# planeReceiverSchem_v2.net
KiCad netlist of a schematic drawn in Altium Designer
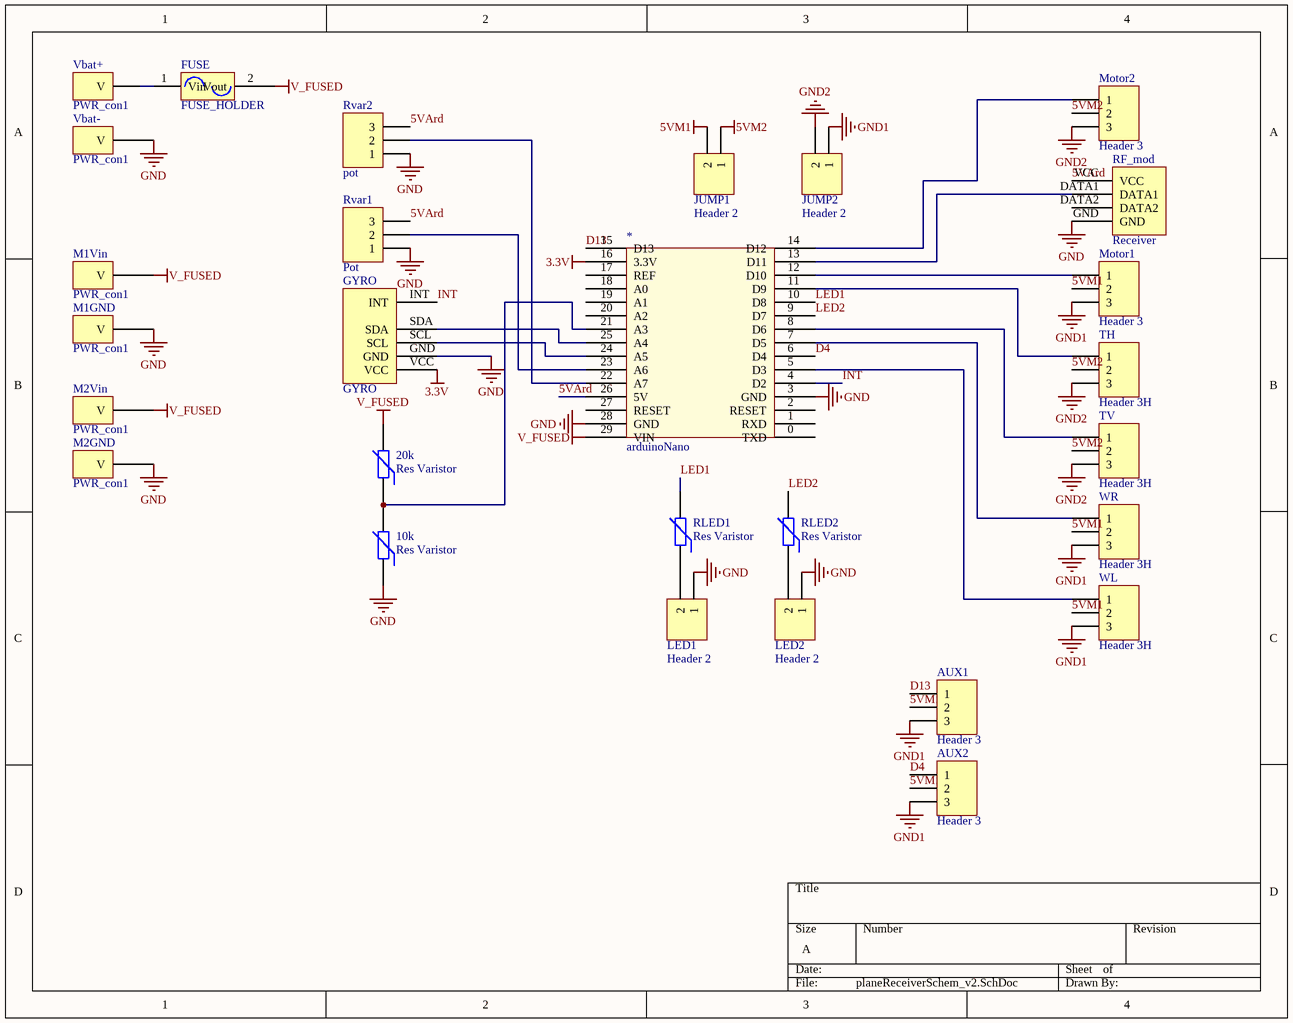
[diagram p0: planeReceiverSchem_v2.SchDoc]

(export (version "E")
  (design (tool "Eeschema 10.0.6"))
  (components
    (comp (ref "*")
      (value "arduinoNano")
      (footprint "Arduino nano")
      (libsource (lib "nanoArduino") (part "arduinoNano"))
    )
    (comp (ref "10k")
      (value "Res Varistor")
      (footprint "6-0805_L")
      (description "Varistor (Voltage-Sensitive Resistor)")
      (fields (field (name "PUBLISHER") "Altium Limited"))
      (libsource (lib "Miscellaneous Devices") (part "Res Varistor"))
    )
    (comp (ref "20k")
      (value "Res Varistor")
      (footprint "6-0805_L")
      (description "Varistor (Voltage-Sensitive Resistor)")
      (fields (field (name "PUBLISHER") "Altium Limited"))
      (libsource (lib "Miscellaneous Devices") (part "Res Varistor"))
    )
    (comp (ref "AUX1")
      (value "Header 3")
      (footprint "HDR1X3")
      (description "Header, 3-Pin")
      (fields (field (name "PUBLISHER") "Altium Limited"))
      (libsource (lib "Miscellaneous Connectors") (part "Header 3"))
    )
    (comp (ref "AUX2")
      (value "Header 3")
      (footprint "HDR1X3")
      (description "Header, 3-Pin")
      (fields (field (name "PUBLISHER") "Altium Limited"))
      (libsource (lib "Miscellaneous Connectors") (part "Header 3"))
    )
    (comp (ref "FUSE")
      (value "FUSE_HOLDER")
      (footprint "FUSE_HOLDER")
      (libsource (lib "nanoArduino") (part "FUSE_HOLDER"))
    )
    (comp (ref "GYRO") (value "GYRO") (footprint "Gyro") (libsource (lib "nanoArduino") (part "GYRO")))
    (comp (ref "JUMP1")
      (value "Header 2")
      (footprint "HDR1X2")
      (description "Header, 2-Pin")
      (fields (field (name "PUBLISHER") "Altium Limited"))
      (libsource (lib "Miscellaneous Connectors") (part "Header 2"))
    )
    (comp (ref "JUMP2")
      (value "Header 2")
      (footprint "HDR1X2")
      (description "Header, 2-Pin")
      (fields (field (name "PUBLISHER") "Altium Limited"))
      (libsource (lib "Miscellaneous Connectors") (part "Header 2"))
    )
    (comp (ref "LED1")
      (value "Header 2")
      (footprint "HDR1X2")
      (description "Header, 2-Pin")
      (fields (field (name "PUBLISHER") "Altium Limited"))
      (libsource (lib "Miscellaneous Connectors") (part "Header 2"))
    )
    (comp (ref "LED2")
      (value "Header 2")
      (footprint "HDR1X2")
      (description "Header, 2-Pin")
      (fields (field (name "PUBLISHER") "Altium Limited"))
      (libsource (lib "Miscellaneous Connectors") (part "Header 2"))
    )
    (comp (ref "M1GND")
      (value "PWR_con1")
      (footprint "PWR_CON_1")
      (libsource (lib "nanoArduino") (part "PWR_con1"))
    )
    (comp (ref "M1Vin")
      (value "PWR_con1")
      (footprint "PWR_CON_1")
      (libsource (lib "nanoArduino") (part "PWR_con1"))
    )
    (comp (ref "M2GND")
      (value "PWR_con1")
      (footprint "PWR_CON_1")
      (libsource (lib "nanoArduino") (part "PWR_con1"))
    )
    (comp (ref "M2Vin")
      (value "PWR_con1")
      (footprint "PWR_CON_1")
      (libsource (lib "nanoArduino") (part "PWR_con1"))
    )
    (comp (ref "Motor1")
      (value "Header 3")
      (footprint "HDR1X3")
      (description "Header, 3-Pin")
      (fields (field (name "PUBLISHER") "Altium Limited"))
      (libsource (lib "Miscellaneous Connectors") (part "Header 3"))
    )
    (comp (ref "Motor2")
      (value "Header 3")
      (footprint "HDR1X3")
      (description "Header, 3-Pin")
      (fields (field (name "PUBLISHER") "Altium Limited"))
      (libsource (lib "Miscellaneous Connectors") (part "Header 3"))
    )
    (comp (ref "RF_mod")
      (value "Receiver")
      (footprint "RF_modue")
      (libsource (lib "nanoArduino") (part "Receiver"))
    )
    (comp (ref "RLED1")
      (value "Res Varistor")
      (footprint "6-0805_L")
      (description "Varistor (Voltage-Sensitive Resistor)")
      (fields (field (name "PUBLISHER") "Altium Limited"))
      (libsource (lib "Miscellaneous Devices") (part "Res Varistor"))
    )
    (comp (ref "RLED2")
      (value "Res Varistor")
      (footprint "6-0805_L")
      (description "Varistor (Voltage-Sensitive Resistor)")
      (fields (field (name "PUBLISHER") "Altium Limited"))
      (libsource (lib "Miscellaneous Devices") (part "Res Varistor"))
    )
    (comp (ref "Rvar1")
      (value "Pot")
      (footprint "HDR1X3")
      (description "Header, 3-Pin")
      (fields (field (name "PUBLISHER") "Altium Limited"))
      (libsource (lib "") (part "Header 3_1"))
    )
    (comp (ref "Rvar2")
      (value "pot")
      (footprint "HDR1X3")
      (description "Header, 3-Pin")
      (fields (field (name "PUBLISHER") "Altium Limited"))
      (libsource (lib "") (part "Header 3_1"))
    )
    (comp (ref "TH")
      (value "Header 3H")
      (footprint "HDR1X3H")
      (description "Header, 3-Pin, Right Angle")
      (fields (field (name "PUBLISHER") "Altium Limited"))
      (libsource (lib "Miscellaneous Connectors") (part "Header 3H"))
    )
    (comp (ref "TV")
      (value "Header 3H")
      (footprint "HDR1X3H")
      (description "Header, 3-Pin, Right Angle")
      (fields (field (name "PUBLISHER") "Altium Limited"))
      (libsource (lib "Miscellaneous Connectors") (part "Header 3H"))
    )
    (comp (ref "Vbat+")
      (value "PWR_con1")
      (footprint "PWR_CON_1")
      (libsource (lib "nanoArduino") (part "PWR_con1"))
    )
    (comp (ref "Vbat-")
      (value "PWR_con1")
      (footprint "PWR_CON_1")
      (libsource (lib "nanoArduino") (part "PWR_con1"))
    )
    (comp (ref "WL")
      (value "Header 3H")
      (footprint "HDR1X3H")
      (description "Header, 3-Pin, Right Angle")
      (fields (field (name "PUBLISHER") "Altium Limited"))
      (libsource (lib "Miscellaneous Connectors") (part "Header 3H"))
    )
    (comp (ref "WR")
      (value "Header 3H")
      (footprint "HDR1X3H")
      (description "Header, 3-Pin, Right Angle")
      (fields (field (name "PUBLISHER") "Altium Limited"))
      (libsource (lib "Miscellaneous Connectors") (part "Header 3H"))
    )
  )
  (nets
    (net (code "1") (name "/5VArd") (class "Default")
      (node (ref "*") (pin "26") (pinfunction "5V_26") (pintype "passive"))
      (node (ref "RF_mod") (pin "VCC") (pinfunction "VCC_VCC") (pintype "passive"))
      (node (ref "Rvar1") (pin "3") (pinfunction "3_3") (pintype "passive"))
      (node (ref "Rvar2") (pin "3") (pinfunction "3_3") (pintype "passive"))
    )
    (net (code "2") (name "/D4") (class "Default")
      (node (ref "*") (pin "6") (pinfunction "D4_6") (pintype "passive"))
      (node (ref "AUX2") (pin "1") (pinfunction "1_1") (pintype "passive"))
    )
    (net (code "3") (name "/D13") (class "Default")
      (node (ref "*") (pin "15") (pinfunction "D13_15") (pintype "passive"))
      (node (ref "AUX1") (pin "1") (pinfunction "1_1") (pintype "passive"))
    )
    (net (code "4") (name "/INT") (class "Default")
      (node (ref "*") (pin "4") (pinfunction "D2_4") (pintype "passive"))
      (node (ref "GYRO") (pin "INT") (pinfunction "INT_INT") (pintype "passive"))
    )
    (net (code "5") (name "/LED1") (class "Default")
      (node (ref "*") (pin "10") (pinfunction "D8_10") (pintype "passive"))
      (node (ref "RLED1") (pin "2") (pinfunction "2_2") (pintype "passive"))
    )
    (net (code "6") (name "/LED2") (class "Default")
      (node (ref "*") (pin "9") (pinfunction "D7_9") (pintype "passive"))
      (node (ref "RLED2") (pin "2") (pinfunction "2_2") (pintype "passive"))
    )
    (net (code "7") (name "3.3V") (class "Default")
      (node (ref "*") (pin "16") (pinfunction "3.3V_16") (pintype "passive"))
      (node (ref "GYRO") (pin "VCC") (pinfunction "VCC_VCC") (pintype "passive"))
    )
    (net (code "8") (name "5VM1") (class "Default")
      (node (ref "AUX1") (pin "2") (pinfunction "2_2") (pintype "passive"))
      (node (ref "AUX2") (pin "2") (pinfunction "2_2") (pintype "passive"))
      (node (ref "JUMP1") (pin "2") (pinfunction "2_2") (pintype "passive"))
      (node (ref "Motor1") (pin "2") (pinfunction "2_2") (pintype "passive"))
      (node (ref "WL") (pin "2") (pinfunction "2_2") (pintype "passive"))
      (node (ref "WR") (pin "2") (pinfunction "2_2") (pintype "passive"))
    )
    (net (code "9") (name "5VM2") (class "Default")
      (node (ref "JUMP1") (pin "1") (pinfunction "1_1") (pintype "passive"))
      (node (ref "Motor2") (pin "2") (pinfunction "2_2") (pintype "passive"))
      (node (ref "TH") (pin "2") (pinfunction "2_2") (pintype "passive"))
      (node (ref "TV") (pin "2") (pinfunction "2_2") (pintype "passive"))
    )
    (net (code "10") (name "GND") (class "Default")
      (node (ref "*") (pin "28") (pinfunction "GND_28") (pintype "passive"))
      (node (ref "*") (pin "3") (pinfunction "GND_3") (pintype "passive"))
      (node (ref "10k") (pin "1") (pinfunction "1_1") (pintype "passive"))
      (node (ref "GYRO") (pin "GND") (pinfunction "GND_GND") (pintype "passive"))
      (node (ref "LED1") (pin "1") (pinfunction "1_1") (pintype "passive"))
      (node (ref "LED2") (pin "1") (pinfunction "1_1") (pintype "passive"))
      (node (ref "M1GND") (pin "0") (pinfunction "V_0") (pintype "passive"))
      (node (ref "M2GND") (pin "0") (pinfunction "V_0") (pintype "passive"))
      (node (ref "RF_mod") (pin "GND") (pinfunction "GND_GND") (pintype "passive"))
      (node (ref "Rvar1") (pin "1") (pinfunction "1_1") (pintype "passive"))
      (node (ref "Rvar2") (pin "1") (pinfunction "1_1") (pintype "passive"))
      (node (ref "Vbat-") (pin "0") (pinfunction "V_0") (pintype "passive"))
    )
    (net (code "11") (name "GND1") (class "Default")
      (node (ref "AUX1") (pin "3") (pinfunction "3_3") (pintype "passive"))
      (node (ref "AUX2") (pin "3") (pinfunction "3_3") (pintype "passive"))
      (node (ref "JUMP2") (pin "1") (pinfunction "1_1") (pintype "passive"))
      (node (ref "Motor1") (pin "3") (pinfunction "3_3") (pintype "passive"))
      (node (ref "WL") (pin "3") (pinfunction "3_3") (pintype "passive"))
      (node (ref "WR") (pin "3") (pinfunction "3_3") (pintype "passive"))
    )
    (net (code "12") (name "GND2") (class "Default")
      (node (ref "JUMP2") (pin "2") (pinfunction "2_2") (pintype "passive"))
      (node (ref "Motor2") (pin "3") (pinfunction "3_3") (pintype "passive"))
      (node (ref "TH") (pin "3") (pinfunction "3_3") (pintype "passive"))
      (node (ref "TV") (pin "3") (pinfunction "3_3") (pintype "passive"))
    )
    (net (code "13") (name "Net-(*-A3)") (class "Default")
      (node (ref "*") (pin "21") (pinfunction "A3_21") (pintype "passive"))
      (node (ref "10k") (pin "2") (pinfunction "2_2") (pintype "passive"))
      (node (ref "20k") (pin "1") (pinfunction "1_1") (pintype "passive"))
    )
    (net (code "14") (name "Net-(*-A4)") (class "Default")
      (node (ref "*") (pin "25") (pinfunction "A4_25") (pintype "passive"))
      (node (ref "GYRO") (pin "SDA") (pinfunction "SDA_SDA") (pintype "passive"))
    )
    (net (code "15") (name "Net-(*-A5)") (class "Default")
      (node (ref "*") (pin "24") (pinfunction "A5_24") (pintype "passive"))
      (node (ref "GYRO") (pin "SCL") (pinfunction "SCL_SCL") (pintype "passive"))
    )
    (net (code "16") (name "Net-(*-A6)") (class "Default")
      (node (ref "*") (pin "23") (pinfunction "A6_23") (pintype "passive"))
      (node (ref "Rvar1") (pin "2") (pinfunction "2_2") (pintype "passive"))
    )
    (net (code "17") (name "Net-(*-A7)") (class "Default")
      (node (ref "*") (pin "22") (pinfunction "A7_22") (pintype "passive"))
      (node (ref "Rvar2") (pin "2") (pinfunction "2_2") (pintype "passive"))
    )
    (net (code "18") (name "Net-(*-D3)") (class "Default")
      (node (ref "*") (pin "5") (pinfunction "D3_5") (pintype "passive"))
      (node (ref "WL") (pin "1") (pinfunction "1_1") (pintype "passive"))
    )
    (net (code "19") (name "Net-(*-D5)") (class "Default")
      (node (ref "*") (pin "7") (pinfunction "D5_7") (pintype "passive"))
      (node (ref "WR") (pin "1") (pinfunction "1_1") (pintype "passive"))
    )
    (net (code "20") (name "Net-(*-D6)") (class "Default")
      (node (ref "*") (pin "8") (pinfunction "D6_8") (pintype "passive"))
      (node (ref "TV") (pin "1") (pinfunction "1_1") (pintype "passive"))
    )
    (net (code "21") (name "Net-(*-D9)") (class "Default")
      (node (ref "*") (pin "11") (pinfunction "D9_11") (pintype "passive"))
      (node (ref "TH") (pin "1") (pinfunction "1_1") (pintype "passive"))
    )
    (net (code "22") (name "Net-(*-D10)") (class "Default")
      (node (ref "*") (pin "12") (pinfunction "D10_12") (pintype "passive"))
      (node (ref "Motor1") (pin "1") (pinfunction "1_1") (pintype "passive"))
    )
    (net (code "23") (name "Net-(*-D11)") (class "Default")
      (node (ref "*") (pin "13") (pinfunction "D11_13") (pintype "passive"))
      (node (ref "RF_mod") (pin "DATA1") (pinfunction "DATA1_DATA1") (pintype "passive"))
    )
    (net (code "24") (name "Net-(*-D12)") (class "Default")
      (node (ref "*") (pin "14") (pinfunction "D12_14") (pintype "passive"))
      (node (ref "Motor2") (pin "1") (pinfunction "1_1") (pintype "passive"))
    )
    (net (code "25") (name "Net-(FUSE-Vin)") (class "Default")
      (node (ref "FUSE") (pin "1") (pinfunction "Vin_1") (pintype "passive"))
      (node (ref "Vbat+") (pin "0") (pinfunction "V_0") (pintype "passive"))
    )
    (net (code "26") (name "Net-(LED1-Pad2)") (class "Default")
      (node (ref "LED1") (pin "2") (pinfunction "2_2") (pintype "passive"))
      (node (ref "RLED1") (pin "1") (pinfunction "1_1") (pintype "passive"))
    )
    (net (code "27") (name "Net-(LED2-Pad2)") (class "Default")
      (node (ref "LED2") (pin "2") (pinfunction "2_2") (pintype "passive"))
      (node (ref "RLED2") (pin "1") (pinfunction "1_1") (pintype "passive"))
    )
    (net (code "28") (name "V_FUSED") (class "Default")
      (node (ref "*") (pin "29") (pinfunction "VIN_29") (pintype "passive"))
      (node (ref "20k") (pin "2") (pinfunction "2_2") (pintype "passive"))
      (node (ref "FUSE") (pin "2") (pinfunction "Vout_2") (pintype "passive"))
      (node (ref "M1Vin") (pin "0") (pinfunction "V_0") (pintype "passive"))
      (node (ref "M2Vin") (pin "0") (pinfunction "V_0") (pintype "passive"))
    )
    (net (code "29") (name "unconnected-(*-A0-Pad18)") (class "Default")
      (node (ref "*") (pin "18") (pinfunction "A0_18") (pintype "passive"))
    )
    (net (code "30") (name "unconnected-(*-A1-Pad19)") (class "Default")
      (node (ref "*") (pin "19") (pinfunction "A1_19") (pintype "passive"))
    )
    (net (code "31") (name "unconnected-(*-A2-Pad20)") (class "Default")
      (node (ref "*") (pin "20") (pinfunction "A2_20") (pintype "passive"))
    )
    (net (code "32") (name "unconnected-(*-REF-Pad17)") (class "Default")
      (node (ref "*") (pin "17") (pinfunction "REF_17") (pintype "passive"))
    )
    (net (code "33") (name "unconnected-(*-RESET-Pad2)") (class "Default")
      (node (ref "*") (pin "2") (pinfunction "RESET_2") (pintype "passive"))
    )
    (net (code "34") (name "unconnected-(*-RESET-Pad27)") (class "Default")
      (node (ref "*") (pin "27") (pinfunction "RESET_27") (pintype "passive"))
    )
    (net (code "35") (name "unconnected-(*-RXD-Pad1)") (class "Default")
      (node (ref "*") (pin "1") (pinfunction "RXD_1") (pintype "passive"))
    )
    (net (code "36") (name "unconnected-(*-TXD-Pad0)") (class "Default")
      (node (ref "*") (pin "0") (pinfunction "TXD_0") (pintype "passive"))
    )
    (net (code "37") (name "unconnected-(RF_mod-PadDATA2)") (class "Default")
      (node (ref "RF_mod") (pin "DATA2") (pinfunction "DATA2_DATA2") (pintype "passive"))
    )
  )
)
